# Ampli_audio.net
KiCad netlist of a schematic drawn in Altium Designer
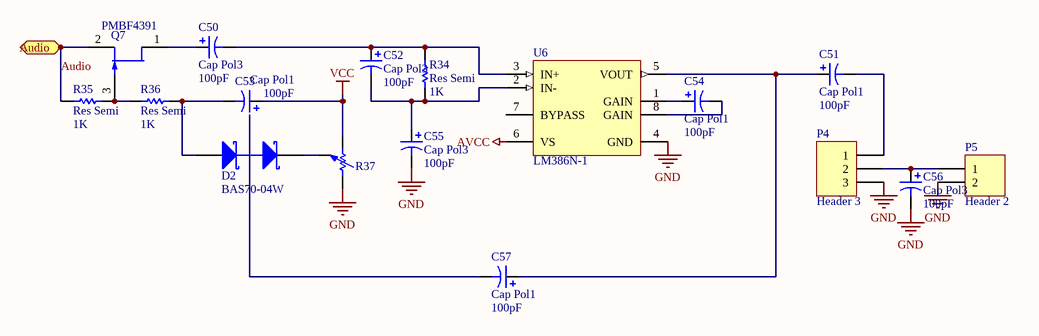
[diagram p0: Ampli_audio.SchDoc]

(export (version "E")
  (design (tool "Eeschema 10.0.6"))
  (components
    (comp (ref "C50")
      (value "Cap Pol3")
      (footprint "C0805")
      (description "Polarized Capacitor (Surface Mount)")
      (fields (field (name "ALTIUM_VALUE") "100pF") (field (name "PUBLISHER") "Altium Limited"))
      (libsource (lib "Miscellaneous Devices") (part "Cap Pol3"))
    )
    (comp (ref "C51")
      (value "Cap Pol1")
      (footprint "B")
      (description "Polarized Capacitor (Radial)")
      (fields (field (name "ALTIUM_VALUE") "100pF") (field (name "PUBLISHER") "Altium Limited"))
      (libsource (lib "Miscellaneous Devices") (part "Cap Pol1"))
    )
    (comp (ref "C52")
      (value "Cap Pol3")
      (footprint "C0805")
      (description "Polarized Capacitor (Surface Mount)")
      (fields (field (name "ALTIUM_VALUE") "100pF") (field (name "PUBLISHER") "Altium Limited"))
      (libsource (lib "Miscellaneous Devices") (part "Cap Pol3"))
    )
    (comp (ref "C53")
      (value "Cap Pol1")
      (footprint "B")
      (description "Polarized Capacitor (Radial)")
      (fields (field (name "ALTIUM_VALUE") "100pF") (field (name "PUBLISHER") "Altium Limited"))
      (libsource (lib "Miscellaneous Devices") (part "Cap Pol1"))
    )
    (comp (ref "C54")
      (value "Cap Pol1")
      (footprint "B")
      (description "Polarized Capacitor (Radial)")
      (fields (field (name "ALTIUM_VALUE") "100pF") (field (name "PUBLISHER") "Altium Limited"))
      (libsource (lib "Miscellaneous Devices") (part "Cap Pol1"))
    )
    (comp (ref "C55")
      (value "Cap Pol3")
      (footprint "C0805")
      (description "Polarized Capacitor (Surface Mount)")
      (fields (field (name "ALTIUM_VALUE") "100pF") (field (name "PUBLISHER") "Altium Limited"))
      (libsource (lib "Miscellaneous Devices") (part "Cap Pol3"))
    )
    (comp (ref "C56")
      (value "Cap Pol3")
      (footprint "C0805")
      (description "Polarized Capacitor (Surface Mount)")
      (fields (field (name "ALTIUM_VALUE") "100pF") (field (name "PUBLISHER") "Altium Limited"))
      (libsource (lib "Miscellaneous Devices") (part "Cap Pol3"))
    )
    (comp (ref "C57")
      (value "Cap Pol1")
      (footprint "B")
      (description "Polarized Capacitor (Radial)")
      (fields (field (name "ALTIUM_VALUE") "100pF") (field (name "PUBLISHER") "Altium Limited"))
      (libsource (lib "Miscellaneous Devices") (part "Cap Pol1"))
    )
    (comp (ref "D2")
      (value "BAS70-04W")
      (footprint "SOT323_N")
      (description "Schottky Barrier Double Diode")
      (fields (field (name "PUBLISHER") "Altium Limited"))
      (libsource (lib "Philips Discrete Diode - Schottky") (part "BAS70-04W"))
    )
    (comp (ref "P4")
      (value "Header 3")
      (footprint "HDR1X3")
      (description "Header, 3-Pin")
      (fields (field (name "PUBLISHER") "Altium Limited"))
      (libsource (lib "Miscellaneous Connectors") (part "Header 3"))
    )
    (comp (ref "P5")
      (value "Header 2")
      (footprint "HDR1X2")
      (description "Header, 2-Pin")
      (fields (field (name "PUBLISHER") "Altium Limited"))
      (libsource (lib "Miscellaneous Connectors") (part "Header 2"))
    )
    (comp (ref "Q7")
      (value "PMBF4391")
      (footprint "SOT23_N")
      (description "N-channel Silicon Junction Field-effect Transistor")
      (fields (field (name "PUBLISHER") "Altium Limited"))
      (libsource (lib "Philips Discrete JFET") (part "PMBF4391"))
    )
    (comp (ref "R34")
      (value "Res Semi")
      (footprint "2012[0805]")
      (description "Semiconductor Resistor")
      (fields (field (name "ALTIUM_VALUE") "1K") (field (name "PUBLISHER") "Altium Limited"))
      (libsource (lib "Miscellaneous Devices") (part "Res Semi"))
    )
    (comp (ref "R35")
      (value "Res Semi")
      (footprint "2012[0805]")
      (description "Semiconductor Resistor")
      (fields (field (name "ALTIUM_VALUE") "1K") (field (name "PUBLISHER") "Altium Limited"))
      (libsource (lib "Miscellaneous Devices") (part "Res Semi"))
    )
    (comp (ref "R36")
      (value "Res Semi")
      (footprint "2012[0805]")
      (description "Semiconductor Resistor")
      (fields (field (name "ALTIUM_VALUE") "1K") (field (name "PUBLISHER") "Altium Limited"))
      (libsource (lib "Miscellaneous Devices") (part "Res Semi"))
    )
    (comp (ref "R37") (value "Pot") (footprint "Potenciometro") (libsource (lib "epf") (part "Pot")))
    (comp (ref "U6")
      (value "LM386N-1")
      (footprint "N08E")
      (description "Low Voltage Audio Power Amplifier")
      (fields
        (field (name "MANUFACTURER") "National Semiconductor")
        (field (name "DIGIKEYPARTNUMBER") "LM386N-1-ND")
      )
      (libsource (lib "NSC Audio") (part "LM386N-1"))
    )
  )
  (nets
    (net (code "1") (name "/Audio") (class "Default")
      (node (ref "Q7") (pin "2") (pinfunction "S_2") (pintype "passive"))
      (node (ref "R35") (pin "1") (pinfunction "1_1") (pintype "passive"))
    )
    (net (code "2") (name "AVCC") (class "Default")
      (node (ref "U6") (pin "6") (pinfunction "VS_6") (pintype "power_in"))
    )
    (net (code "3") (name "GND") (class "Default")
      (node (ref "C55") (pin "2") (pinfunction "2_2") (pintype "passive"))
      (node (ref "C56") (pin "2") (pinfunction "2_2") (pintype "passive"))
      (node (ref "P4") (pin "3") (pinfunction "3_3") (pintype "passive"))
      (node (ref "P5") (pin "2") (pinfunction "2_2") (pintype "passive"))
      (node (ref "R37") (pin "1") (pinfunction "1_1") (pintype "passive"))
      (node (ref "U6") (pin "4") (pinfunction "GND_4") (pintype "power_in"))
    )
    (net (code "4") (name "Net-(C51-Pad2)") (class "Default")
      (node (ref "C51") (pin "2") (pinfunction "2_2") (pintype "passive"))
      (node (ref "P4") (pin "1") (pinfunction "1_1") (pintype "passive"))
    )
    (net (code "5") (name "Net-(C54-Pad1)") (class "Default")
      (node (ref "C54") (pin "1") (pinfunction "1_1") (pintype "passive"))
      (node (ref "U6") (pin "1") (pinfunction "GAIN_1") (pintype "passive"))
    )
    (net (code "6") (name "Net-(C54-Pad2)") (class "Default")
      (node (ref "C54") (pin "2") (pinfunction "2_2") (pintype "passive"))
      (node (ref "U6") (pin "8") (pinfunction "GAIN_8") (pintype "passive"))
    )
    (net (code "7") (name "Net-(C56-Pad1)") (class "Default")
      (node (ref "C56") (pin "1") (pinfunction "1_1") (pintype "passive"))
      (node (ref "P4") (pin "2") (pinfunction "2_2") (pintype "passive"))
      (node (ref "P5") (pin "1") (pinfunction "1_1") (pintype "passive"))
    )
    (net (code "8") (name "Net-(D2-A)") (class "Default")
      (node (ref "C53") (pin "2") (pinfunction "2_2") (pintype "passive"))
      (node (ref "D2") (pin "1") (pinfunction "A_1") (pintype "passive"))
      (node (ref "R36") (pin "2") (pinfunction "2_2") (pintype "passive"))
    )
    (net (code "9") (name "Net-(D2-C)") (class "Default")
      (node (ref "C57") (pin "2") (pinfunction "2_2") (pintype "passive"))
      (node (ref "D2") (pin "3") (pinfunction "C_3") (pintype "passive"))
    )
    (net (code "10") (name "Net-(D2-K)") (class "Default")
      (node (ref "D2") (pin "2") (pinfunction "K_2") (pintype "passive"))
      (node (ref "R37") (pin "3") (pinfunction "3_3") (pintype "passive"))
    )
    (net (code "11") (name "Net-(Q7-D)") (class "Default")
      (node (ref "C50") (pin "1") (pinfunction "1_1") (pintype "passive"))
      (node (ref "Q7") (pin "1") (pinfunction "D_1") (pintype "passive"))
    )
    (net (code "12") (name "Net-(Q7-G)") (class "Default")
      (node (ref "Q7") (pin "3") (pinfunction "G_3") (pintype "passive"))
      (node (ref "R35") (pin "2") (pinfunction "2_2") (pintype "passive"))
      (node (ref "R36") (pin "1") (pinfunction "1_1") (pintype "passive"))
    )
    (net (code "13") (name "Net-(U6-IN+)") (class "Default")
      (node (ref "C50") (pin "2") (pinfunction "2_2") (pintype "passive"))
      (node (ref "C52") (pin "1") (pinfunction "1_1") (pintype "passive"))
      (node (ref "R34") (pin "2") (pinfunction "2_2") (pintype "passive"))
      (node (ref "U6") (pin "3") (pinfunction "IN+_3") (pintype "input"))
    )
    (net (code "14") (name "Net-(U6-IN-)") (class "Default")
      (node (ref "C52") (pin "2") (pinfunction "2_2") (pintype "passive"))
      (node (ref "C55") (pin "1") (pinfunction "1_1") (pintype "passive"))
      (node (ref "R34") (pin "1") (pinfunction "1_1") (pintype "passive"))
      (node (ref "U6") (pin "2") (pinfunction "IN-_2") (pintype "input"))
    )
    (net (code "15") (name "Net-(U6-VOUT)") (class "Default")
      (node (ref "C51") (pin "1") (pinfunction "1_1") (pintype "passive"))
      (node (ref "C57") (pin "1") (pinfunction "1_1") (pintype "passive"))
      (node (ref "U6") (pin "5") (pinfunction "VOUT_5") (pintype "output"))
    )
    (net (code "16") (name "VCC") (class "Default")
      (node (ref "C53") (pin "1") (pinfunction "1_1") (pintype "passive"))
      (node (ref "R37") (pin "2") (pinfunction "2_2") (pintype "passive"))
    )
    (net (code "17") (name "unconnected-(U6-BYPASS-Pad7)") (class "Default")
      (node (ref "U6") (pin "7") (pinfunction "BYPASS_7") (pintype "passive"))
    )
  )
)
